# SimPL_IMU_v1_0__OCT31.net
KiCad netlist of a schematic drawn in Altium Designer
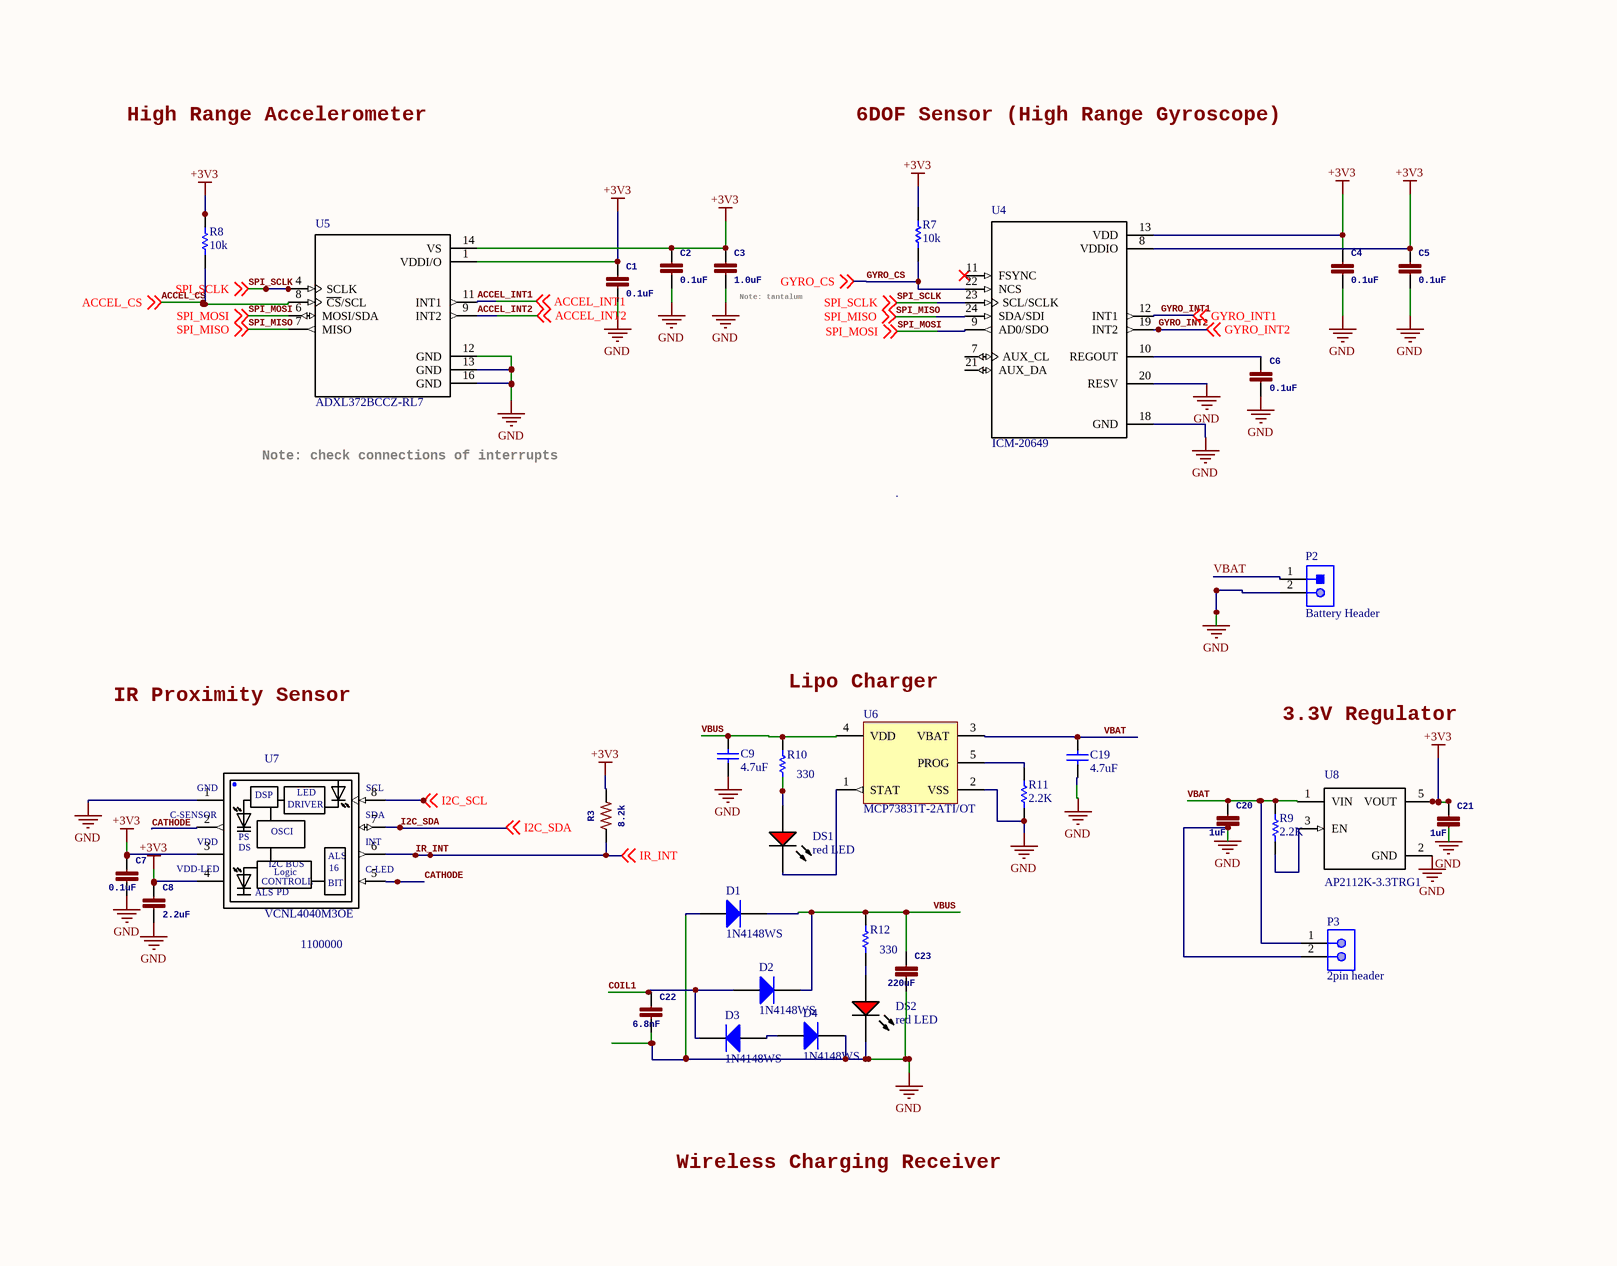
[diagram p0: SimPL_IMU_v1_0 _OCT31.SchDoc]

(export (version "E")
  (design (tool "Eeschema 10.0.6"))
  (components
    (comp (ref "C1")
      (value "0.1uF")
      (footprint "0402")
      (libsource (lib "SparkFun-Capacitors") (part "0.1UF-0402-16V-10%"))
    )
    (comp (ref "C2")
      (value "0.1uF")
      (footprint "0402")
      (libsource (lib "SparkFun-Capacitors") (part "0.1UF-0402-16V-10%"))
    )
    (comp (ref "C3")
      (value "1.0uF")
      (footprint "0402")
      (libsource (lib "SparkFun-Capacitors") (part "1.0UF-0402-16V-10%"))
    )
    (comp (ref "C4")
      (value "0.1uF")
      (footprint "0402")
      (libsource (lib "SparkFun-Capacitors") (part "0.1UF-0402-16V-10%"))
    )
    (comp (ref "C5")
      (value "0.1uF")
      (footprint "0402")
      (libsource (lib "SparkFun-Capacitors") (part "0.1UF-0402-16V-10%"))
    )
    (comp (ref "C6")
      (value "0.1uF")
      (footprint "0402")
      (libsource (lib "SparkFun-Capacitors") (part "0.1UF-0402-16V-10%"))
    )
    (comp (ref "C7")
      (value "0.1uF")
      (footprint "0402")
      (libsource (lib "SparkFun-Capacitors") (part "0.1UF-0402-16V-10%"))
    )
    (comp (ref "C8")
      (value "2.2uF")
      (footprint "0402")
      (libsource (lib "SparkFun-Capacitors") (part "0.1UF-0402-16V-10%"))
    )
    (comp (ref "C9")
      (value "4.7uF")
      (footprint "CAPC1005X65X10ML15")
      (description "Chip Capacitor, 4.7 uF, +/- 20%, 10 V, -55 to 85 degC, 0402 (1005 Metric), RoHS, Tape and Reel")
      (fields
        (field (name "TOLERANCE") "±20%")
        (field (name "PCN PART NUMBER") "MLCCPartNumberChange30/Nov/2012")
      )
      (libsource (lib "Altium Content Vault") (part "CAP-NP-2"))
    )
    (comp (ref "C19")
      (value "4.7uF")
      (footprint "CAPC1005X65X10ML15")
      (description "Chip Capacitor, 4.7 uF, +/- 20%, 10 V, -55 to 85 degC, 0402 (1005 Metric), RoHS, Tape and Reel")
      (fields
        (field (name "TOLERANCE") "±20%")
        (field (name "PCN PART NUMBER") "MLCCPartNumberChange30/Nov/2012")
      )
      (libsource (lib "Altium Content Vault") (part "CAP-NP-2"))
    )
    (comp (ref "C20")
      (value "1uF")
      (footprint "0402")
      (libsource (lib "SparkFun-Capacitors") (part "0.1UF-0402-16V-10%"))
    )
    (comp (ref "C21")
      (value "1uF")
      (footprint "0402")
      (libsource (lib "SparkFun-Capacitors") (part "0.1UF-0402-16V-10%"))
    )
    (comp (ref "C22")
      (value "6.8nF")
      (footprint "0402")
      (libsource (lib "SparkFun-Capacitors") (part "0.1UF-0402-16V-10%"))
    )
    (comp (ref "C23")
      (value "220uF")
      (footprint "0402")
      (libsource (lib "SparkFun-Capacitors") (part "0.1UF-0402-16V-10%"))
    )
    (comp (ref "D1")
      (value "1N4148WS")
      (footprint "DIOD-SOD323-2-A_V")
      (description "Fast Switching Diode, 75 V, 0.3 A, -65 to 150 degC, 2-Pin SOD323, RoHS, Tape and Reel")
      (libsource (lib "Altium Content Vault") (part "D-AK-2"))
    )
    (comp (ref "D2")
      (value "1N4148WS")
      (footprint "DIOD-SOD323-2-A_V")
      (description "Fast Switching Diode, 75 V, 0.3 A, -65 to 150 degC, 2-Pin SOD323, RoHS, Tape and Reel")
      (libsource (lib "Altium Content Vault") (part "D-AK-2"))
    )
    (comp (ref "D3")
      (value "1N4148WS")
      (footprint "DIOD-SOD323-2-A_V")
      (description "Fast Switching Diode, 75 V, 0.3 A, -65 to 150 degC, 2-Pin SOD323, RoHS, Tape and Reel")
      (libsource (lib "Altium Content Vault") (part "D-AK-2"))
    )
    (comp (ref "D4")
      (value "1N4148WS")
      (footprint "DIOD-SOD323-2-A_V")
      (description "Fast Switching Diode, 75 V, 0.3 A, -65 to 150 degC, 2-Pin SOD323, RoHS, Tape and Reel")
      (libsource (lib "Altium Content Vault") (part "D-AK-2"))
    )
    (comp (ref "DS1")
      (value "red LED")
      (footprint "VISH-TLMS1000_V")
      (description "Low Current LED, 40 mW, 1.8 V, -40 to 100 degC, 2-Pin SMD (0603), RoHS, Tape and Reel")
      (fields (field (name "MANUFACTURER") "Vishay"))
      (libsource (lib "Altium Content Vault") (part "LED-RED-AK-2"))
    )
    (comp (ref "DS2")
      (value "red LED")
      (footprint "VISH-TLMS1000_V")
      (description "Low Current LED, 40 mW, 1.8 V, -40 to 100 degC, 2-Pin SMD (0603), RoHS, Tape and Reel")
      (fields (field (name "MANUFACTURER") "Vishay"))
      (libsource (lib "Altium Content Vault") (part "LED-RED-AK-2"))
    )
    (comp (ref "P2")
      (value "Battery Header")
      (footprint "JST-S2B-PH-K-S_V")
      (fields (field (name "TOLERANCE") "20%"))
      (libsource (lib "Altium Content Vault") (part "CN-1P-M-R2"))
    )
    (comp (ref "P3")
      (value "2pin header")
      (footprint "AMPH-68000-102HLF_V")
      (description "Male Header, Pitch 2.54 mm, 1 x 2 Position, Height 8.38 mm, Tail Length 2.41 mm, RoHS, Bulk")
      (fields (field (name "MANUFACTURER") "FCI"))
      (libsource (lib "") (part "CN-1P-M-R2_1"))
    )
    (comp (ref "R3")
      (value "8.2k")
      (footprint "0603")
      (libsource (lib "SparkFun-Resistors") (part "8.2KOHM-0603-1/10W-5%"))
    )
    (comp (ref "R7")
      (value "10k")
      (footprint "RESC1005X40X25NL05T05")
      (description "Chip Resistor, 10 KOhm, +/- 1%, 100 mW, -55 to 155 degC, 0402 (1005 Metric), RoHS, Tape and Reel")
      (fields (field (name "MANUFACTURER") "Basic Passives") (field (name "TOLERANCE") "1%"))
      (libsource (lib "Altium Content Vault") (part "RES-2"))
    )
    (comp (ref "R8")
      (value "10k")
      (footprint "RESC1005X40X25NL05T05")
      (description "Chip Resistor, 10 KOhm, +/- 1%, 100 mW, -55 to 155 degC, 0402 (1005 Metric), RoHS, Tape and Reel")
      (fields (field (name "MANUFACTURER") "Basic Passives") (field (name "TOLERANCE") "1%"))
      (libsource (lib "Altium Content Vault") (part "RES-2"))
    )
    (comp (ref "R9")
      (value "2.2K")
      (footprint "RESC1005X40X25ML10T10")
      (fields (field (name "PART NUMBER") "MC00625W040212K2") (field (name "MANUFACTURER") "Multicomp"))
      (libsource (lib "Altium Content Vault") (part "RES"))
    )
    (comp (ref "R10")
      (value "330")
      (footprint "RESC2013X50X30NL20T20")
      (fields (field (name "MANUFACTURER") "Vishay Dale") (field (name "PART NUMBER") "CRCW0805330RFKEA"))
      (libsource (lib "Altium Content Vault") (part "RES"))
    )
    (comp (ref "R11")
      (value "2.2K")
      (footprint "RESC1005X40X25ML10T10")
      (fields (field (name "PART NUMBER") "MC00625W040212K2") (field (name "MANUFACTURER") "Multicomp"))
      (libsource (lib "Altium Content Vault") (part "RES"))
    )
    (comp (ref "R12")
      (value "330")
      (footprint "RESC2013X50X30NL20T20")
      (fields (field (name "MANUFACTURER") "Vishay Dale") (field (name "PART NUMBER") "CRCW0805330RFKEA"))
      (libsource (lib "Altium Content Vault") (part "RES"))
    )
    (comp (ref "U4")
      (value "ICM-20649")
      (footprint "*QFN40P300X300X95-24N")
      (description "Wide-Range 6-Axis MEMS MotionTracking Device for Sports and High Impact Applications")
      (fields (field (name "MF") "TDK InvenSense"))
      (libsource (lib "ICM-20649") (part "ICM-20649"))
    )
    (comp (ref "U5")
      (value "ADXL372BCCZ-RL7")
      (footprint "*PQFN50P322X300X114-16N")
      (description "Accelerometer Triple Â±200g 2.5V 16-Pin LGA T/R")
      (fields (field (name "MF") "Analog Devices"))
      (libsource (lib "ADXL372BCCZ-RL7") (part "ADXL372BCCZ-RL7"))
    )
    (comp (ref "U6")
      (value "MCP73831T-2ATI/OT")
      (footprint "SOT-23-OT5_M")
      (libsource (lib "Altium Content Vault") (part "PM-BM-MCP73831-SOT5"))
    )
    (comp (ref "U7")
      (value "VCNL4040M3OE")
      (footprint "*VISHAY_VCNL4040_4X2X1.1")
      (description "VCNL4040 Series 3.6 V 200 mm 16 Bit I2C SMT Proximity and Ambient Light Sensor")
      (fields (field (name "MF") "Vishay"))
      (libsource (lib "VCNL4040M3OE") (part "VCNL4040M3OE"))
    )
    (comp (ref "U8")
      (value "AP2112K-3.3TRG1")
      (footprint "*SOT95P285X140-5N")
      (description "AP2112 Series 0.6 A 3.3 V Fixed Output SMT LDO Linear Regulator - SOT23-5")
      (fields (field (name "MF") "Diodes Inc."))
      (libsource (lib "AP2112K-3.3TRG1") (part "AP2112K-3.3TRG1"))
    )
  )
  (nets
    (net (code "1") (name "+3V3") (class "Default")
      (node (ref "C1") (pin "1") (pinfunction "1_1") (pintype "passive"))
      (node (ref "C2") (pin "1") (pinfunction "1_1") (pintype "passive"))
      (node (ref "C21") (pin "1") (pinfunction "1_1") (pintype "passive"))
      (node (ref "C3") (pin "1") (pinfunction "1_1") (pintype "passive"))
      (node (ref "C4") (pin "1") (pinfunction "1_1") (pintype "passive"))
      (node (ref "C5") (pin "1") (pinfunction "1_1") (pintype "passive"))
      (node (ref "C7") (pin "1") (pinfunction "1_1") (pintype "passive"))
      (node (ref "C8") (pin "1") (pinfunction "1_1") (pintype "passive"))
      (node (ref "R3") (pin "2") (pinfunction "2_2") (pintype "passive"))
      (node (ref "R7") (pin "2") (pinfunction "2_2") (pintype "passive"))
      (node (ref "R8") (pin "2") (pinfunction "2_2") (pintype "passive"))
      (node (ref "U4") (pin "13") (pinfunction "VDD_13") (pintype "power_in"))
      (node (ref "U4") (pin "8") (pinfunction "VDDIO_8") (pintype "power_in"))
      (node (ref "U5") (pin "1") (pinfunction "VDDI/O_1") (pintype "power_in"))
      (node (ref "U5") (pin "14") (pinfunction "VS_14") (pintype "power_in"))
      (node (ref "U7") (pin "3") (pinfunction "VDD_3") (pintype "power_in"))
      (node (ref "U7") (pin "4") (pinfunction "VDD-LED_4") (pintype "power_in"))
      (node (ref "U8") (pin "5") (pinfunction "VOUT_5") (pintype "power_in"))
    )
    (net (code "2") (name "/CATHODE") (class "Default")
      (node (ref "U7") (pin "2") (pinfunction "C-SENSOR_2") (pintype "output"))
      (node (ref "U7") (pin "5") (pinfunction "C-LED_5") (pintype "input"))
    )
    (net (code "3") (name "/COIL1") (class "Default")
      (node (ref "C22") (pin "1") (pinfunction "1_1") (pintype "passive"))
      (node (ref "D2") (pin "1") (pinfunction "A_1") (pintype "passive"))
      (node (ref "D3") (pin "2") (pinfunction "K_2") (pintype "passive"))
    )
    (net (code "4") (name "/VBAT") (class "Default")
      (node (ref "C19") (pin "2") (pinfunction "2_2") (pintype "passive"))
      (node (ref "C20") (pin "1") (pinfunction "1_1") (pintype "passive"))
      (node (ref "P2") (pin "1") (pinfunction "1_1") (pintype "passive"))
      (node (ref "P3") (pin "1") (pinfunction "1_1") (pintype "passive"))
      (node (ref "R9") (pin "2") (pinfunction "2_2") (pintype "passive"))
      (node (ref "U6") (pin "3") (pinfunction "VBAT_3") (pintype "power_in"))
      (node (ref "U8") (pin "1") (pinfunction "VIN_1") (pintype "power_in"))
    )
    (net (code "5") (name "/VBUS") (class "Default")
      (node (ref "C23") (pin "1") (pinfunction "1_1") (pintype "passive"))
      (node (ref "C9") (pin "2") (pinfunction "2_2") (pintype "passive"))
      (node (ref "D1") (pin "2") (pinfunction "K_2") (pintype "passive"))
      (node (ref "D2") (pin "2") (pinfunction "K_2") (pintype "passive"))
      (node (ref "R10") (pin "2") (pinfunction "2_2") (pintype "passive"))
      (node (ref "R12") (pin "2") (pinfunction "2_2") (pintype "passive"))
      (node (ref "U6") (pin "4") (pinfunction "VDD_4") (pintype "power_in"))
    )
    (net (code "6") (name "ACCEL_CS") (class "Default")
      (node (ref "R8") (pin "1") (pinfunction "1_1") (pintype "passive"))
      (node (ref "U5") (pin "8") (pinfunction "~{CS}/SCL_8") (pintype "input"))
    )
    (net (code "7") (name "ACCEL_INT1") (class "Default")
      (node (ref "U5") (pin "11") (pinfunction "INT1_11") (pintype "output"))
    )
    (net (code "8") (name "ACCEL_INT2") (class "Default")
      (node (ref "U5") (pin "9") (pinfunction "INT2_9") (pintype "output"))
    )
    (net (code "9") (name "GND") (class "Default")
      (node (ref "C1") (pin "2") (pinfunction "2_2") (pintype "passive"))
      (node (ref "C19") (pin "1") (pinfunction "1_1") (pintype "passive"))
      (node (ref "C2") (pin "2") (pinfunction "2_2") (pintype "passive"))
      (node (ref "C20") (pin "2") (pinfunction "2_2") (pintype "passive"))
      (node (ref "C21") (pin "2") (pinfunction "2_2") (pintype "passive"))
      (node (ref "C22") (pin "2") (pinfunction "2_2") (pintype "passive"))
      (node (ref "C23") (pin "2") (pinfunction "2_2") (pintype "passive"))
      (node (ref "C3") (pin "2") (pinfunction "2_2") (pintype "passive"))
      (node (ref "C4") (pin "2") (pinfunction "2_2") (pintype "passive"))
      (node (ref "C5") (pin "2") (pinfunction "2_2") (pintype "passive"))
      (node (ref "C6") (pin "2") (pinfunction "2_2") (pintype "passive"))
      (node (ref "C7") (pin "2") (pinfunction "2_2") (pintype "passive"))
      (node (ref "C8") (pin "2") (pinfunction "2_2") (pintype "passive"))
      (node (ref "C9") (pin "1") (pinfunction "1_1") (pintype "passive"))
      (node (ref "D1") (pin "1") (pinfunction "A_1") (pintype "passive"))
      (node (ref "D4") (pin "2") (pinfunction "K_2") (pintype "passive"))
      (node (ref "DS2") (pin "2") (pinfunction "K_2") (pintype "passive"))
      (node (ref "P2") (pin "2") (pinfunction "2_2") (pintype "passive"))
      (node (ref "P3") (pin "2") (pinfunction "2_2") (pintype "passive"))
      (node (ref "R11") (pin "1") (pinfunction "1_1") (pintype "passive"))
      (node (ref "U4") (pin "18") (pinfunction "GND_18") (pintype "power_in"))
      (node (ref "U4") (pin "20") (pinfunction "RESV_20") (pintype "passive"))
      (node (ref "U5") (pin "12") (pinfunction "GND_12") (pintype "power_in"))
      (node (ref "U5") (pin "13") (pinfunction "GND_13") (pintype "power_in"))
      (node (ref "U5") (pin "16") (pinfunction "GND_16") (pintype "power_in"))
      (node (ref "U6") (pin "2") (pinfunction "VSS_2") (pintype "power_in"))
      (node (ref "U7") (pin "1") (pinfunction "GND_1") (pintype "power_in"))
      (node (ref "U8") (pin "2") (pinfunction "GND_2") (pintype "power_in"))
    )
    (net (code "10") (name "GYRO_CS") (class "Default")
      (node (ref "R7") (pin "1") (pinfunction "1_1") (pintype "passive"))
      (node (ref "U4") (pin "22") (pinfunction "NCS_22") (pintype "input"))
    )
    (net (code "11") (name "GYRO_INT1") (class "Default")
      (node (ref "U4") (pin "12") (pinfunction "INT1_12") (pintype "output"))
    )
    (net (code "12") (name "GYRO_INT2") (class "Default")
      (node (ref "U4") (pin "19") (pinfunction "INT2_19") (pintype "output"))
    )
    (net (code "13") (name "I2C_SCL") (class "Default")
      (node (ref "U7") (pin "8") (pinfunction "SCL_8") (pintype "input"))
    )
    (net (code "14") (name "I2C_SDA") (class "Default")
      (node (ref "U7") (pin "7") (pinfunction "SDA_7") (pintype "bidirectional"))
    )
    (net (code "15") (name "IR_INT") (class "Default")
      (node (ref "R3") (pin "1") (pinfunction "1_1") (pintype "passive"))
      (node (ref "U7") (pin "6") (pinfunction "INT_6") (pintype "output"))
    )
    (net (code "16") (name "Net-(D3-A)") (class "Default")
      (node (ref "D3") (pin "1") (pinfunction "A_1") (pintype "passive"))
      (node (ref "D4") (pin "1") (pinfunction "A_1") (pintype "passive"))
    )
    (net (code "17") (name "Net-(DS1-A)") (class "Default")
      (node (ref "DS1") (pin "1") (pinfunction "A_1") (pintype "passive"))
      (node (ref "R10") (pin "1") (pinfunction "1_1") (pintype "passive"))
    )
    (net (code "18") (name "Net-(DS1-K)") (class "Default")
      (node (ref "DS1") (pin "2") (pinfunction "K_2") (pintype "passive"))
      (node (ref "U6") (pin "1") (pinfunction "STAT_1") (pintype "output"))
    )
    (net (code "19") (name "Net-(DS2-A)") (class "Default")
      (node (ref "DS2") (pin "1") (pinfunction "A_1") (pintype "passive"))
      (node (ref "R12") (pin "1") (pinfunction "1_1") (pintype "passive"))
    )
    (net (code "20") (name "Net-(U4-REGOUT)") (class "Default")
      (node (ref "C6") (pin "1") (pinfunction "1_1") (pintype "passive"))
      (node (ref "U4") (pin "10") (pinfunction "REGOUT_10") (pintype "passive"))
    )
    (net (code "21") (name "Net-(U6-PROG)") (class "Default")
      (node (ref "R11") (pin "2") (pinfunction "2_2") (pintype "passive"))
      (node (ref "U6") (pin "5") (pinfunction "PROG_5") (pintype "passive"))
    )
    (net (code "22") (name "Net-(U8-EN)") (class "Default")
      (node (ref "R9") (pin "1") (pinfunction "1_1") (pintype "passive"))
      (node (ref "U8") (pin "3") (pinfunction "EN_3") (pintype "input"))
    )
    (net (code "23") (name "SPI_MISO") (class "Default")
      (node (ref "U4") (pin "24") (pinfunction "SDA/SDI_24") (pintype "input"))
      (node (ref "U5") (pin "7") (pinfunction "MISO_7") (pintype "output"))
    )
    (net (code "24") (name "SPI_MOSI") (class "Default")
      (node (ref "U4") (pin "9") (pinfunction "AD0/SDO_9") (pintype "output"))
      (node (ref "U5") (pin "6") (pinfunction "MOSI/SDA_6") (pintype "bidirectional"))
    )
    (net (code "25") (name "SPI_SCLK") (class "Default")
      (node (ref "U4") (pin "23") (pinfunction "SCL/SCLK_23") (pintype "input"))
      (node (ref "U5") (pin "4") (pinfunction "SCLK_4") (pintype "input"))
    )
    (net (code "26") (name "unconnected-(U4-AUX_CL-Pad7)") (class "Default")
      (node (ref "U4") (pin "7") (pinfunction "AUX_CL_7") (pintype "bidirectional"))
    )
    (net (code "27") (name "unconnected-(U4-AUX_DA-Pad21)") (class "Default")
      (node (ref "U4") (pin "21") (pinfunction "AUX_DA_21") (pintype "bidirectional"))
    )
    (net (code "28") (name "unconnected-(U4-FSYNC-Pad11)") (class "Default")
      (node (ref "U4") (pin "11") (pinfunction "FSYNC_11") (pintype "input+no_connect"))
    )
  )
)
